# umodular_mega_shield_rev02.net
KiCad netlist of a schematic drawn in EAGLE
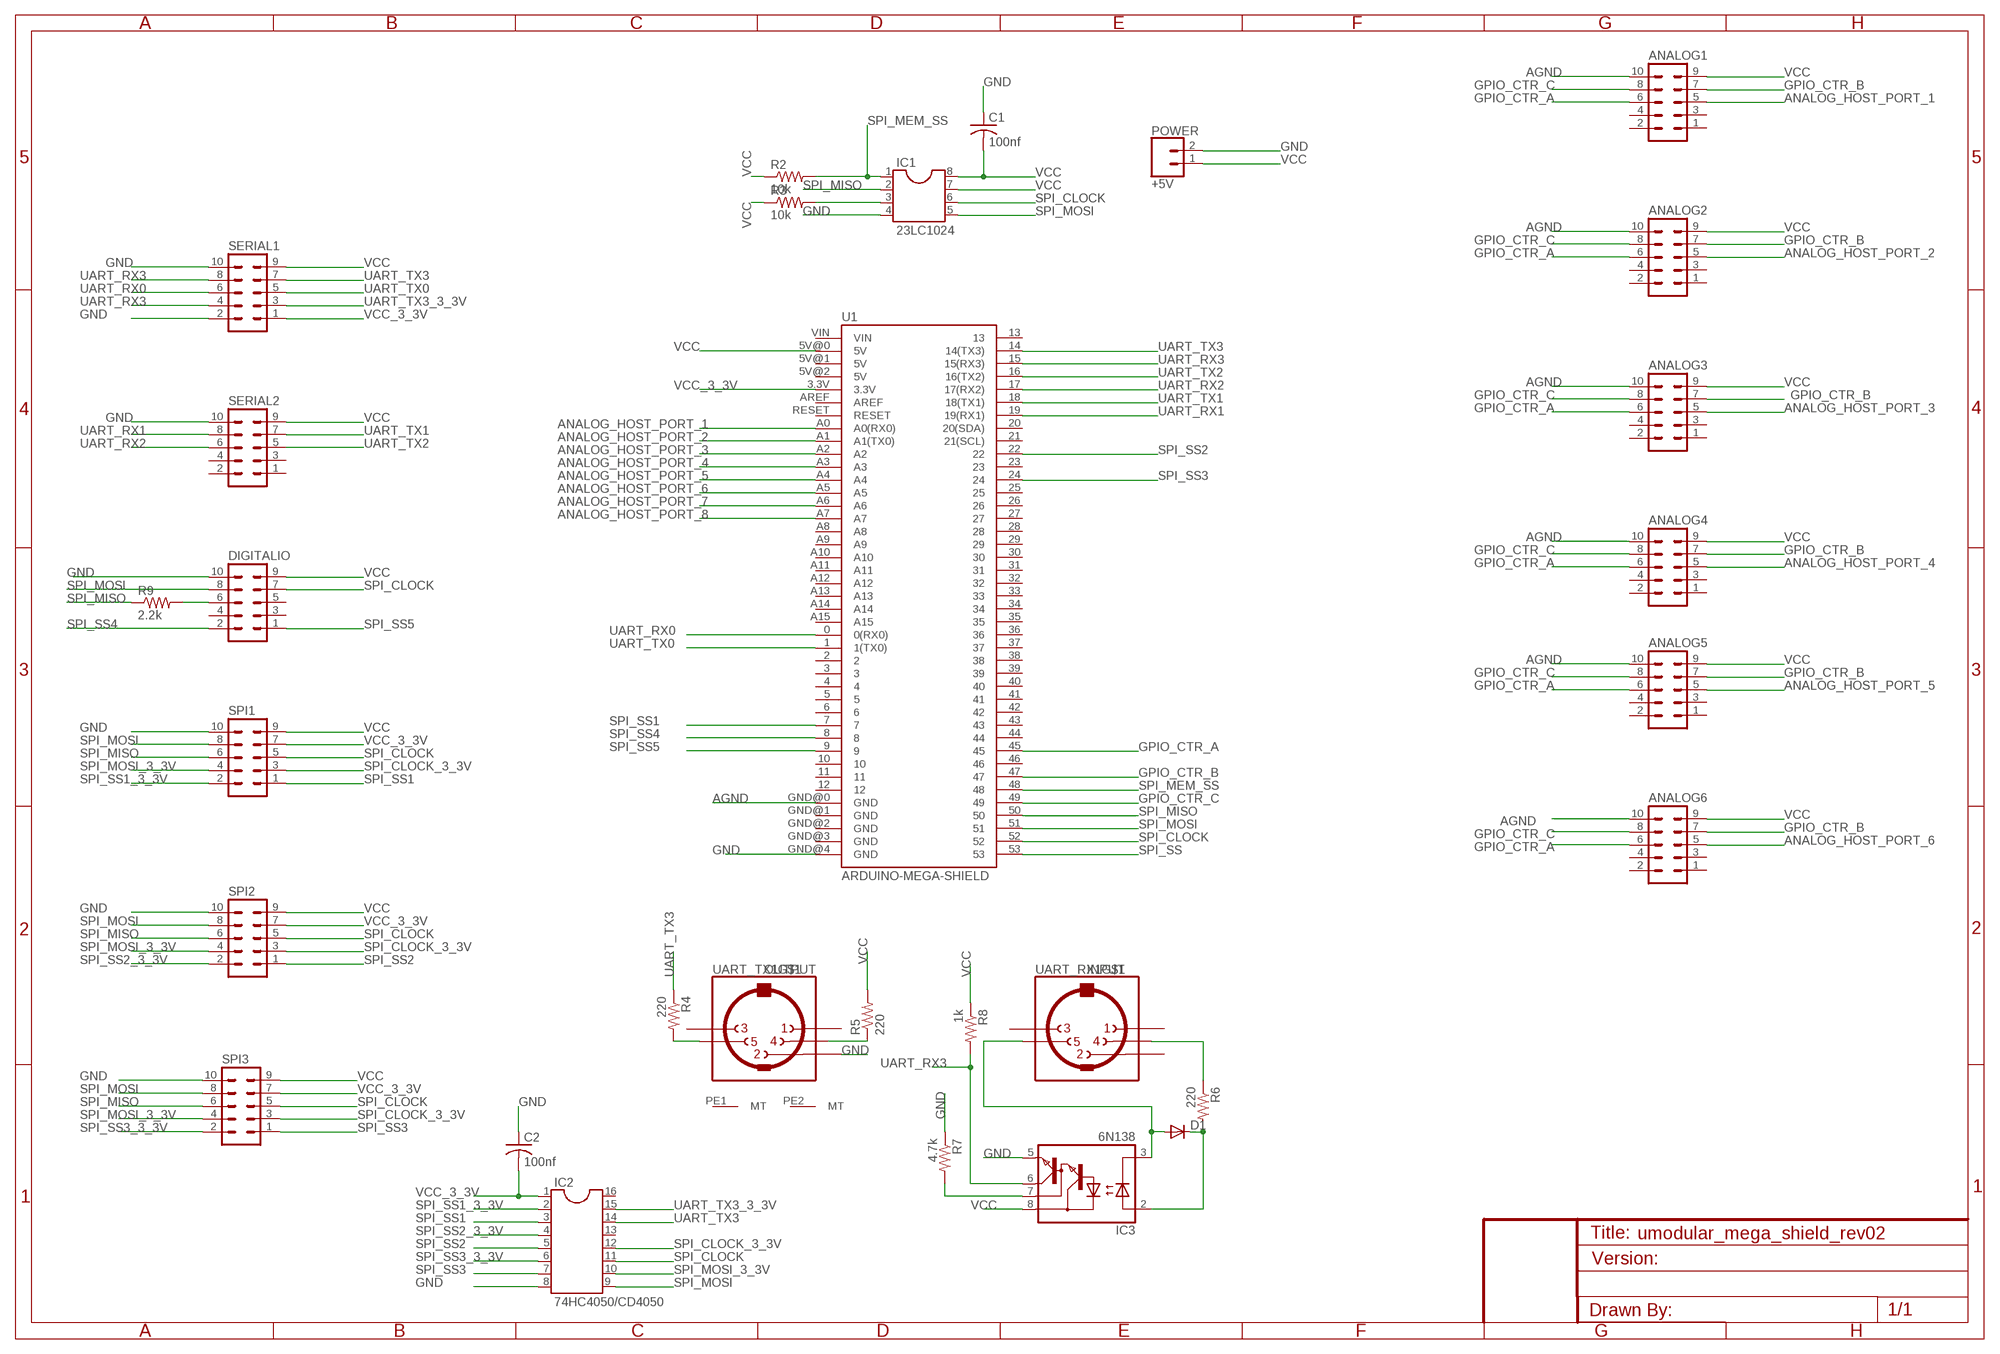
[diagram p0: schematic, sheet 1]

(export (version "E")
  (design (tool "Eeschema 10.0.6"))
  (components
    (comp (ref "ANALOG1")
      (value "MA05-2")
      (footprint "eagle-import:MA05-2")
      (libsource (lib "eagle-import") (part "MA05-2"))
    )
    (comp (ref "ANALOG2")
      (value "MA05-2")
      (footprint "eagle-import:MA05-2")
      (libsource (lib "eagle-import") (part "MA05-2"))
    )
    (comp (ref "ANALOG3")
      (value "MA05-2")
      (footprint "eagle-import:MA05-2")
      (libsource (lib "eagle-import") (part "MA05-2"))
    )
    (comp (ref "ANALOG4")
      (value "MA05-2")
      (footprint "eagle-import:MA05-2")
      (libsource (lib "eagle-import") (part "MA05-2"))
    )
    (comp (ref "ANALOG5")
      (value "MA05-2")
      (footprint "eagle-import:MA05-2")
      (libsource (lib "eagle-import") (part "MA05-2"))
    )
    (comp (ref "ANALOG6")
      (value "MA05-2")
      (footprint "eagle-import:MA05-2")
      (libsource (lib "eagle-import") (part "MA05-2"))
    )
    (comp (ref "C1")
      (value "100nf")
      (footprint "eagle-import:C050-024X044")
      (libsource (lib "eagle-import") (part "C-US050-024X044"))
    )
    (comp (ref "C2")
      (value "100nf")
      (footprint "eagle-import:C050-024X044")
      (libsource (lib "eagle-import") (part "C-US050-024X044"))
    )
    (comp (ref "D1")
      (value "1N4148DO35-7")
      (footprint "eagle-import:DO35-7")
      (libsource (lib "eagle-import") (part "1N4148DO35-7"))
    )
    (comp (ref "DIGITALIO")
      (value "MA05-2")
      (footprint "eagle-import:MA05-2")
      (libsource (lib "eagle-import") (part "MA05-2"))
    )
    (comp (ref "IC1")
      (value "23LC1024")
      (footprint "eagle-import:DIL08")
      (libsource (lib "eagle-import") (part "DIL8"))
    )
    (comp (ref "IC2")
      (value "74HC4050/CD4050")
      (footprint "eagle-import:DIL16")
      (libsource (lib "eagle-import") (part "DIL16"))
    )
    (comp (ref "IC3")
      (value "6N138")
      (footprint "eagle-import:DIL08")
      (fields (field (name "MF") "VISHAY/TELEFUNKEN"))
      (libsource (lib "eagle-import") (part "6N138"))
    )
    (comp (ref "POWER")
      (value "+5V")
      (footprint "eagle-import:1X02_LOCK_LONGPADS")
      (libsource (lib "eagle-import") (part "CONN_02LOCK_LONGPADS"))
    )
    (comp (ref "R2")
      (value "10k")
      (footprint "eagle-import:0204_7@1")
      (libsource (lib "eagle-import") (part "R-US_0204/7"))
    )
    (comp (ref "R3")
      (value "10k")
      (footprint "eagle-import:0204_7@1")
      (libsource (lib "eagle-import") (part "R-US_0204/7"))
    )
    (comp (ref "R4")
      (value "220")
      (footprint "eagle-import:0204_7@1")
      (libsource (lib "eagle-import") (part "R-US_0204/7"))
    )
    (comp (ref "R5")
      (value "220")
      (footprint "eagle-import:0204_7@1")
      (libsource (lib "eagle-import") (part "R-US_0204/7"))
    )
    (comp (ref "R6")
      (value "220")
      (footprint "eagle-import:0204_7@1")
      (libsource (lib "eagle-import") (part "R-US_0204/7"))
    )
    (comp (ref "R7")
      (value "4.7k")
      (footprint "eagle-import:0204_7@1")
      (libsource (lib "eagle-import") (part "R-US_0204/7"))
    )
    (comp (ref "R8")
      (value "1k")
      (footprint "eagle-import:0204_7@1")
      (libsource (lib "eagle-import") (part "R-US_0204/7"))
    )
    (comp (ref "R9")
      (value "2.2k")
      (footprint "eagle-import:0204_7@1")
      (libsource (lib "eagle-import") (part "R-US_0204/7"))
    )
    (comp (ref "SERIAL1")
      (value "MA05-2")
      (footprint "eagle-import:MA05-2")
      (libsource (lib "eagle-import") (part "MA05-2"))
    )
    (comp (ref "SERIAL2")
      (value "MA05-2")
      (footprint "eagle-import:MA05-2")
      (libsource (lib "eagle-import") (part "MA05-2"))
    )
    (comp (ref "SPI1")
      (value "MA05-2")
      (footprint "eagle-import:MA05-2")
      (libsource (lib "eagle-import") (part "MA05-2"))
    )
    (comp (ref "SPI2")
      (value "MA05-2")
      (footprint "eagle-import:MA05-2")
      (libsource (lib "eagle-import") (part "MA05-2"))
    )
    (comp (ref "SPI3")
      (value "MA05-2")
      (footprint "eagle-import:MA05-2")
      (libsource (lib "eagle-import") (part "MA05-2"))
    )
    (comp (ref "U1")
      (value "ARDUINO-MEGA-SHIELD")
      (footprint "eagle-import:ARDUINO_MEGA@1")
      (libsource (lib "eagle-import") (part "ARDUINO-MEGAFULL"))
    )
    (comp (ref "UART_RX1")
      (value "INPUT")
      (footprint "eagle-import:CP-2350")
      (libsource (lib "eagle-import") (part "MIDIJACK"))
    )
    (comp (ref "UART_TX1")
      (value "OUTPUT")
      (footprint "eagle-import:CP-2350")
      (libsource (lib "eagle-import") (part "MIDIJACK"))
    )
  )
  (nets
    (net (code "1") (name "/AGND") (class "Default")
      (node (ref "ANALOG1") (pin "10") (pinfunction "10_10") (pintype "passive"))
      (node (ref "ANALOG2") (pin "10") (pinfunction "10_10") (pintype "passive"))
      (node (ref "ANALOG3") (pin "10") (pinfunction "10_10") (pintype "passive"))
      (node (ref "ANALOG4") (pin "10") (pinfunction "10_10") (pintype "passive"))
      (node (ref "ANALOG5") (pin "10") (pinfunction "10_10") (pintype "passive"))
      (node (ref "ANALOG6") (pin "10") (pinfunction "10_10") (pintype "passive"))
      (node (ref "U1") (pin "GND@0") (pinfunction "GND_GND@0") (pintype "bidirectional"))
    )
    (net (code "2") (name "/ANALOG_HOST_PORT_1") (class "Default")
      (node (ref "ANALOG1") (pin "5") (pinfunction "5_5") (pintype "passive"))
      (node (ref "U1") (pin "A0") (pinfunction "A0(RX0)_A0") (pintype "bidirectional"))
    )
    (net (code "3") (name "/ANALOG_HOST_PORT_2") (class "Default")
      (node (ref "ANALOG2") (pin "5") (pinfunction "5_5") (pintype "passive"))
      (node (ref "U1") (pin "A1") (pinfunction "A1(TX0)_A1") (pintype "bidirectional"))
    )
    (net (code "4") (name "/ANALOG_HOST_PORT_3") (class "Default")
      (node (ref "ANALOG3") (pin "5") (pinfunction "5_5") (pintype "passive"))
      (node (ref "U1") (pin "A2") (pinfunction "A2_A2") (pintype "bidirectional"))
    )
    (net (code "5") (name "/ANALOG_HOST_PORT_4") (class "Default")
      (node (ref "ANALOG4") (pin "5") (pinfunction "5_5") (pintype "passive"))
      (node (ref "U1") (pin "A3") (pinfunction "A3_A3") (pintype "bidirectional"))
    )
    (net (code "6") (name "/ANALOG_HOST_PORT_5") (class "Default")
      (node (ref "ANALOG5") (pin "5") (pinfunction "5_5") (pintype "passive"))
      (node (ref "U1") (pin "A4") (pinfunction "A4_A4") (pintype "bidirectional"))
    )
    (net (code "7") (name "/ANALOG_HOST_PORT_6") (class "Default")
      (node (ref "ANALOG6") (pin "5") (pinfunction "5_5") (pintype "passive"))
      (node (ref "U1") (pin "A5") (pinfunction "A5_A5") (pintype "bidirectional"))
    )
    (net (code "8") (name "/ANALOG_HOST_PORT_7") (class "Default")
      (node (ref "U1") (pin "A6") (pinfunction "A6_A6") (pintype "bidirectional"))
    )
    (net (code "9") (name "/ANALOG_HOST_PORT_8") (class "Default")
      (node (ref "U1") (pin "A7") (pinfunction "A7_A7") (pintype "bidirectional"))
    )
    (net (code "10") (name "/GND") (class "Default")
      (node (ref "C1") (pin "1") (pinfunction "1_1") (pintype "passive"))
      (node (ref "C2") (pin "1") (pinfunction "1_1") (pintype "passive"))
      (node (ref "DIGITALIO") (pin "10") (pinfunction "10_10") (pintype "passive"))
      (node (ref "IC1") (pin "4") (pinfunction "4_4") (pintype "passive"))
      (node (ref "IC2") (pin "8") (pinfunction "8_8") (pintype "passive"))
      (node (ref "IC3") (pin "5") (pinfunction "GND_5") (pintype "passive"))
      (node (ref "POWER") (pin "2") (pinfunction "2_2") (pintype "passive"))
      (node (ref "R7") (pin "1") (pinfunction "1_1") (pintype "passive"))
      (node (ref "SERIAL1") (pin "10") (pinfunction "10_10") (pintype "passive"))
      (node (ref "SERIAL1") (pin "2") (pinfunction "2_2") (pintype "passive"))
      (node (ref "SERIAL2") (pin "10") (pinfunction "10_10") (pintype "passive"))
      (node (ref "SPI1") (pin "10") (pinfunction "10_10") (pintype "passive"))
      (node (ref "SPI2") (pin "10") (pinfunction "10_10") (pintype "passive"))
      (node (ref "SPI3") (pin "10") (pinfunction "10_10") (pintype "passive"))
      (node (ref "U1") (pin "GND@4") (pinfunction "GND_GND@4") (pintype "bidirectional"))
      (node (ref "UART_TX1") (pin "2") (pinfunction "2_2") (pintype "passive"))
    )
    (net (code "11") (name "/GPIO_CTR_A") (class "Default")
      (node (ref "ANALOG1") (pin "6") (pinfunction "6_6") (pintype "passive"))
      (node (ref "ANALOG2") (pin "6") (pinfunction "6_6") (pintype "passive"))
      (node (ref "ANALOG3") (pin "6") (pinfunction "6_6") (pintype "passive"))
      (node (ref "ANALOG4") (pin "6") (pinfunction "6_6") (pintype "passive"))
      (node (ref "ANALOG5") (pin "6") (pinfunction "6_6") (pintype "passive"))
      (node (ref "ANALOG6") (pin "6") (pinfunction "6_6") (pintype "passive"))
      (node (ref "U1") (pin "45") (pinfunction "45_45") (pintype "bidirectional"))
    )
    (net (code "12") (name "/GPIO_CTR_B") (class "Default")
      (node (ref "ANALOG1") (pin "7") (pinfunction "7_7") (pintype "passive"))
      (node (ref "ANALOG2") (pin "7") (pinfunction "7_7") (pintype "passive"))
      (node (ref "ANALOG3") (pin "7") (pinfunction "7_7") (pintype "passive"))
      (node (ref "ANALOG4") (pin "7") (pinfunction "7_7") (pintype "passive"))
      (node (ref "ANALOG5") (pin "7") (pinfunction "7_7") (pintype "passive"))
      (node (ref "ANALOG6") (pin "7") (pinfunction "7_7") (pintype "passive"))
      (node (ref "U1") (pin "47") (pinfunction "47_47") (pintype "bidirectional"))
    )
    (net (code "13") (name "/GPIO_CTR_C") (class "Default")
      (node (ref "ANALOG1") (pin "8") (pinfunction "8_8") (pintype "passive"))
      (node (ref "ANALOG2") (pin "8") (pinfunction "8_8") (pintype "passive"))
      (node (ref "ANALOG3") (pin "8") (pinfunction "8_8") (pintype "passive"))
      (node (ref "ANALOG4") (pin "8") (pinfunction "8_8") (pintype "passive"))
      (node (ref "ANALOG5") (pin "8") (pinfunction "8_8") (pintype "passive"))
      (node (ref "ANALOG6") (pin "8") (pinfunction "8_8") (pintype "passive"))
      (node (ref "U1") (pin "49") (pinfunction "49_49") (pintype "bidirectional"))
    )
    (net (code "14") (name "/SPI_CLOCK") (class "Default")
      (node (ref "DIGITALIO") (pin "7") (pinfunction "7_7") (pintype "passive"))
      (node (ref "IC1") (pin "6") (pinfunction "6_6") (pintype "passive"))
      (node (ref "IC2") (pin "11") (pinfunction "11_11") (pintype "passive"))
      (node (ref "SPI1") (pin "5") (pinfunction "5_5") (pintype "passive"))
      (node (ref "SPI2") (pin "5") (pinfunction "5_5") (pintype "passive"))
      (node (ref "SPI3") (pin "5") (pinfunction "5_5") (pintype "passive"))
      (node (ref "U1") (pin "52") (pinfunction "52_52") (pintype "bidirectional"))
    )
    (net (code "15") (name "/SPI_CLOCK_3_3V") (class "Default")
      (node (ref "IC2") (pin "12") (pinfunction "12_12") (pintype "passive"))
      (node (ref "SPI1") (pin "3") (pinfunction "3_3") (pintype "passive"))
      (node (ref "SPI2") (pin "3") (pinfunction "3_3") (pintype "passive"))
      (node (ref "SPI3") (pin "3") (pinfunction "3_3") (pintype "passive"))
    )
    (net (code "16") (name "/SPI_MEM_SS") (class "Default")
      (node (ref "IC1") (pin "1") (pinfunction "1_1") (pintype "passive"))
      (node (ref "R2") (pin "2") (pinfunction "2_2") (pintype "passive"))
      (node (ref "U1") (pin "48") (pinfunction "48_48") (pintype "bidirectional"))
    )
    (net (code "17") (name "/SPI_MISO") (class "Default")
      (node (ref "IC1") (pin "2") (pinfunction "2_2") (pintype "passive"))
      (node (ref "R9") (pin "1") (pinfunction "1_1") (pintype "passive"))
      (node (ref "SPI1") (pin "6") (pinfunction "6_6") (pintype "passive"))
      (node (ref "SPI2") (pin "6") (pinfunction "6_6") (pintype "passive"))
      (node (ref "SPI3") (pin "6") (pinfunction "6_6") (pintype "passive"))
      (node (ref "U1") (pin "50") (pinfunction "50_50") (pintype "bidirectional"))
    )
    (net (code "18") (name "/SPI_MOSI") (class "Default")
      (node (ref "DIGITALIO") (pin "8") (pinfunction "8_8") (pintype "passive"))
      (node (ref "IC1") (pin "5") (pinfunction "5_5") (pintype "passive"))
      (node (ref "IC2") (pin "9") (pinfunction "9_9") (pintype "passive"))
      (node (ref "SPI1") (pin "8") (pinfunction "8_8") (pintype "passive"))
      (node (ref "SPI2") (pin "8") (pinfunction "8_8") (pintype "passive"))
      (node (ref "SPI3") (pin "8") (pinfunction "8_8") (pintype "passive"))
      (node (ref "U1") (pin "51") (pinfunction "51_51") (pintype "bidirectional"))
    )
    (net (code "19") (name "/SPI_MOSI_3_3V") (class "Default")
      (node (ref "IC2") (pin "10") (pinfunction "10_10") (pintype "passive"))
      (node (ref "SPI1") (pin "4") (pinfunction "4_4") (pintype "passive"))
      (node (ref "SPI2") (pin "4") (pinfunction "4_4") (pintype "passive"))
      (node (ref "SPI3") (pin "4") (pinfunction "4_4") (pintype "passive"))
    )
    (net (code "20") (name "/SPI_SS") (class "Default")
      (node (ref "U1") (pin "53") (pinfunction "53_53") (pintype "bidirectional"))
    )
    (net (code "21") (name "/SPI_SS1") (class "Default")
      (node (ref "IC2") (pin "3") (pinfunction "3_3") (pintype "passive"))
      (node (ref "SPI1") (pin "1") (pinfunction "1_1") (pintype "passive"))
      (node (ref "U1") (pin "7") (pinfunction "7_7") (pintype "bidirectional"))
    )
    (net (code "22") (name "/SPI_SS1_3_3V") (class "Default")
      (node (ref "IC2") (pin "2") (pinfunction "2_2") (pintype "passive"))
      (node (ref "SPI1") (pin "2") (pinfunction "2_2") (pintype "passive"))
    )
    (net (code "23") (name "/SPI_SS2") (class "Default")
      (node (ref "IC2") (pin "5") (pinfunction "5_5") (pintype "passive"))
      (node (ref "SPI2") (pin "1") (pinfunction "1_1") (pintype "passive"))
      (node (ref "U1") (pin "22") (pinfunction "22_22") (pintype "bidirectional"))
    )
    (net (code "24") (name "/SPI_SS2_3_3V") (class "Default")
      (node (ref "IC2") (pin "4") (pinfunction "4_4") (pintype "passive"))
      (node (ref "SPI2") (pin "2") (pinfunction "2_2") (pintype "passive"))
    )
    (net (code "25") (name "/SPI_SS3") (class "Default")
      (node (ref "IC2") (pin "7") (pinfunction "7_7") (pintype "passive"))
      (node (ref "SPI3") (pin "1") (pinfunction "1_1") (pintype "passive"))
      (node (ref "U1") (pin "24") (pinfunction "24_24") (pintype "bidirectional"))
    )
    (net (code "26") (name "/SPI_SS3_3_3V") (class "Default")
      (node (ref "IC2") (pin "6") (pinfunction "6_6") (pintype "passive"))
      (node (ref "SPI3") (pin "2") (pinfunction "2_2") (pintype "passive"))
    )
    (net (code "27") (name "/SPI_SS4") (class "Default")
      (node (ref "DIGITALIO") (pin "2") (pinfunction "2_2") (pintype "passive"))
      (node (ref "U1") (pin "8") (pinfunction "8_8") (pintype "bidirectional"))
    )
    (net (code "28") (name "/SPI_SS5") (class "Default")
      (node (ref "DIGITALIO") (pin "1") (pinfunction "1_1") (pintype "passive"))
      (node (ref "U1") (pin "9") (pinfunction "9_9") (pintype "bidirectional"))
    )
    (net (code "29") (name "/UART_RX0") (class "Default")
      (node (ref "SERIAL1") (pin "6") (pinfunction "6_6") (pintype "passive"))
      (node (ref "U1") (pin "0") (pinfunction "0(RX0)_0") (pintype "bidirectional"))
    )
    (net (code "30") (name "/UART_RX1") (class "Default")
      (node (ref "SERIAL2") (pin "8") (pinfunction "8_8") (pintype "passive"))
      (node (ref "U1") (pin "19") (pinfunction "19(RX1)_19") (pintype "bidirectional"))
    )
    (net (code "31") (name "/UART_RX2") (class "Default")
      (node (ref "SERIAL2") (pin "6") (pinfunction "6_6") (pintype "passive"))
      (node (ref "U1") (pin "17") (pinfunction "17(RX2)_17") (pintype "bidirectional"))
    )
    (net (code "32") (name "/UART_RX3") (class "Default")
      (node (ref "IC3") (pin "6") (pinfunction "VO_6") (pintype "passive"))
      (node (ref "R8") (pin "2") (pinfunction "2_2") (pintype "passive"))
      (node (ref "SERIAL1") (pin "4") (pinfunction "4_4") (pintype "passive"))
      (node (ref "SERIAL1") (pin "8") (pinfunction "8_8") (pintype "passive"))
      (node (ref "U1") (pin "15") (pinfunction "15(RX3)_15") (pintype "bidirectional"))
    )
    (net (code "33") (name "/UART_TX0") (class "Default")
      (node (ref "SERIAL1") (pin "5") (pinfunction "5_5") (pintype "passive"))
      (node (ref "U1") (pin "1") (pinfunction "1(TX0)_1") (pintype "bidirectional"))
    )
    (net (code "34") (name "/UART_TX1") (class "Default")
      (node (ref "SERIAL2") (pin "7") (pinfunction "7_7") (pintype "passive"))
      (node (ref "U1") (pin "18") (pinfunction "18(TX1)_18") (pintype "bidirectional"))
    )
    (net (code "35") (name "/UART_TX2") (class "Default")
      (node (ref "SERIAL2") (pin "5") (pinfunction "5_5") (pintype "passive"))
      (node (ref "U1") (pin "16") (pinfunction "16(TX2)_16") (pintype "bidirectional"))
    )
    (net (code "36") (name "/UART_TX3") (class "Default")
      (node (ref "IC2") (pin "14") (pinfunction "14_14") (pintype "passive"))
      (node (ref "R4") (pin "1") (pinfunction "1_1") (pintype "passive"))
      (node (ref "SERIAL1") (pin "7") (pinfunction "7_7") (pintype "passive"))
      (node (ref "U1") (pin "14") (pinfunction "14(TX3)_14") (pintype "bidirectional"))
    )
    (net (code "37") (name "/UART_TX3_3_3V") (class "Default")
      (node (ref "IC2") (pin "15") (pinfunction "15_15") (pintype "passive"))
      (node (ref "SERIAL1") (pin "3") (pinfunction "3_3") (pintype "passive"))
    )
    (net (code "38") (name "/VCC") (class "Default")
      (node (ref "ANALOG1") (pin "9") (pinfunction "9_9") (pintype "passive"))
      (node (ref "ANALOG2") (pin "9") (pinfunction "9_9") (pintype "passive"))
      (node (ref "ANALOG3") (pin "9") (pinfunction "9_9") (pintype "passive"))
      (node (ref "ANALOG4") (pin "9") (pinfunction "9_9") (pintype "passive"))
      (node (ref "ANALOG5") (pin "9") (pinfunction "9_9") (pintype "passive"))
      (node (ref "ANALOG6") (pin "9") (pinfunction "9_9") (pintype "passive"))
      (node (ref "C1") (pin "2") (pinfunction "2_2") (pintype "passive"))
      (node (ref "DIGITALIO") (pin "9") (pinfunction "9_9") (pintype "passive"))
      (node (ref "IC1") (pin "7") (pinfunction "7_7") (pintype "passive"))
      (node (ref "IC1") (pin "8") (pinfunction "8_8") (pintype "passive"))
      (node (ref "IC3") (pin "8") (pinfunction "VCC_8") (pintype "passive"))
      (node (ref "POWER") (pin "1") (pinfunction "1_1") (pintype "passive"))
      (node (ref "R2") (pin "1") (pinfunction "1_1") (pintype "passive"))
      (node (ref "R3") (pin "1") (pinfunction "1_1") (pintype "passive"))
      (node (ref "R5") (pin "2") (pinfunction "2_2") (pintype "passive"))
      (node (ref "R8") (pin "1") (pinfunction "1_1") (pintype "passive"))
      (node (ref "SERIAL1") (pin "9") (pinfunction "9_9") (pintype "passive"))
      (node (ref "SERIAL2") (pin "9") (pinfunction "9_9") (pintype "passive"))
      (node (ref "SPI1") (pin "9") (pinfunction "9_9") (pintype "passive"))
      (node (ref "SPI2") (pin "9") (pinfunction "9_9") (pintype "passive"))
      (node (ref "SPI3") (pin "9") (pinfunction "9_9") (pintype "passive"))
      (node (ref "U1") (pin "5V@0") (pinfunction "5V_5V@0") (pintype "bidirectional"))
    )
    (net (code "39") (name "/VCC_3_3V") (class "Default")
      (node (ref "C2") (pin "2") (pinfunction "2_2") (pintype "passive"))
      (node (ref "IC2") (pin "1") (pinfunction "1_1") (pintype "passive"))
      (node (ref "SERIAL1") (pin "1") (pinfunction "1_1") (pintype "passive"))
      (node (ref "SPI1") (pin "7") (pinfunction "7_7") (pintype "passive"))
      (node (ref "SPI2") (pin "7") (pinfunction "7_7") (pintype "passive"))
      (node (ref "SPI3") (pin "7") (pinfunction "7_7") (pintype "passive"))
      (node (ref "U1") (pin "3.3V") (pinfunction "3.3V_3.3V") (pintype "bidirectional"))
    )
    (net (code "40") (name "Net-(DIGITALIO-Pad6)") (class "Default")
      (node (ref "DIGITALIO") (pin "6") (pinfunction "6_6") (pintype "passive"))
      (node (ref "R9") (pin "2") (pinfunction "2_2") (pintype "passive"))
    )
    (net (code "41") (name "Net-(IC1-Pad3)") (class "Default")
      (node (ref "IC1") (pin "3") (pinfunction "3_3") (pintype "passive"))
      (node (ref "R3") (pin "2") (pinfunction "2_2") (pintype "passive"))
    )
    (net (code "42") (name "Net-(IC3-A)") (class "Default")
      (node (ref "D1") (pin "C") (pinfunction "C_C") (pintype "passive"))
      (node (ref "IC3") (pin "2") (pinfunction "A_2") (pintype "passive"))
      (node (ref "R6") (pin "2") (pinfunction "2_2") (pintype "passive"))
    )
    (net (code "43") (name "Net-(IC3-C)") (class "Default")
      (node (ref "D1") (pin "A") (pinfunction "A_A") (pintype "passive"))
      (node (ref "IC3") (pin "3") (pinfunction "C_3") (pintype "passive"))
      (node (ref "UART_RX1") (pin "5") (pinfunction "5_5") (pintype "passive"))
    )
    (net (code "44") (name "Net-(IC3-VB)") (class "Default")
      (node (ref "IC3") (pin "7") (pinfunction "VB_7") (pintype "passive"))
      (node (ref "R7") (pin "2") (pinfunction "2_2") (pintype "passive"))
    )
    (net (code "45") (name "Net-(R4-Pad2)") (class "Default")
      (node (ref "R4") (pin "2") (pinfunction "2_2") (pintype "passive"))
      (node (ref "UART_TX1") (pin "5") (pinfunction "5_5") (pintype "passive"))
    )
    (net (code "46") (name "Net-(R5-Pad1)") (class "Default")
      (node (ref "R5") (pin "1") (pinfunction "1_1") (pintype "passive"))
      (node (ref "UART_TX1") (pin "4") (pinfunction "4_4") (pintype "passive"))
    )
    (net (code "47") (name "Net-(R6-Pad1)") (class "Default")
      (node (ref "R6") (pin "1") (pinfunction "1_1") (pintype "passive"))
      (node (ref "UART_RX1") (pin "4") (pinfunction "4_4") (pintype "passive"))
    )
    (net (code "48") (name "unconnected-(ANALOG1-Pad1)") (class "Default")
      (node (ref "ANALOG1") (pin "1") (pinfunction "1_1") (pintype "passive"))
    )
    (net (code "49") (name "unconnected-(ANALOG1-Pad2)") (class "Default")
      (node (ref "ANALOG1") (pin "2") (pinfunction "2_2") (pintype "passive"))
    )
    (net (code "50") (name "unconnected-(ANALOG1-Pad3)") (class "Default")
      (node (ref "ANALOG1") (pin "3") (pinfunction "3_3") (pintype "passive"))
    )
    (net (code "51") (name "unconnected-(ANALOG1-Pad4)") (class "Default")
      (node (ref "ANALOG1") (pin "4") (pinfunction "4_4") (pintype "passive"))
    )
    (net (code "52") (name "unconnected-(ANALOG2-Pad1)") (class "Default")
      (node (ref "ANALOG2") (pin "1") (pinfunction "1_1") (pintype "passive"))
    )
    (net (code "53") (name "unconnected-(ANALOG2-Pad2)") (class "Default")
      (node (ref "ANALOG2") (pin "2") (pinfunction "2_2") (pintype "passive"))
    )
    (net (code "54") (name "unconnected-(ANALOG2-Pad3)") (class "Default")
      (node (ref "ANALOG2") (pin "3") (pinfunction "3_3") (pintype "passive"))
    )
    (net (code "55") (name "unconnected-(ANALOG2-Pad4)") (class "Default")
      (node (ref "ANALOG2") (pin "4") (pinfunction "4_4") (pintype "passive"))
    )
    (net (code "56") (name "unconnected-(ANALOG3-Pad1)") (class "Default")
      (node (ref "ANALOG3") (pin "1") (pinfunction "1_1") (pintype "passive"))
    )
    (net (code "57") (name "unconnected-(ANALOG3-Pad2)") (class "Default")
      (node (ref "ANALOG3") (pin "2") (pinfunction "2_2") (pintype "passive"))
    )
    (net (code "58") (name "unconnected-(ANALOG3-Pad3)") (class "Default")
      (node (ref "ANALOG3") (pin "3") (pinfunction "3_3") (pintype "passive"))
    )
    (net (code "59") (name "unconnected-(ANALOG3-Pad4)") (class "Default")
      (node (ref "ANALOG3") (pin "4") (pinfunction "4_4") (pintype "passive"))
    )
    (net (code "60") (name "unconnected-(ANALOG4-Pad1)") (class "Default")
      (node (ref "ANALOG4") (pin "1") (pinfunction "1_1") (pintype "passive"))
    )
    (net (code "61") (name "unconnected-(ANALOG4-Pad2)") (class "Default")
      (node (ref "ANALOG4") (pin "2") (pinfunction "2_2") (pintype "passive"))
    )
    (net (code "62") (name "unconnected-(ANALOG4-Pad3)") (class "Default")
      (node (ref "ANALOG4") (pin "3") (pinfunction "3_3") (pintype "passive"))
    )
    (net (code "63") (name "unconnected-(ANALOG4-Pad4)") (class "Default")
      (node (ref "ANALOG4") (pin "4") (pinfunction "4_4") (pintype "passive"))
    )
    (net (code "64") (name "unconnected-(ANALOG5-Pad1)") (class "Default")
      (node (ref "ANALOG5") (pin "1") (pinfunction "1_1") (pintype "passive"))
    )
    (net (code "65") (name "unconnected-(ANALOG5-Pad2)") (class "Default")
      (node (ref "ANALOG5") (pin "2") (pinfunction "2_2") (pintype "passive"))
    )
    (net (code "66") (name "unconnected-(ANALOG5-Pad3)") (class "Default")
      (node (ref "ANALOG5") (pin "3") (pinfunction "3_3") (pintype "passive"))
    )
    (net (code "67") (name "unconnected-(ANALOG5-Pad4)") (class "Default")
      (node (ref "ANALOG5") (pin "4") (pinfunction "4_4") (pintype "passive"))
    )
    (net (code "68") (name "unconnected-(ANALOG6-Pad1)") (class "Default")
      (node (ref "ANALOG6") (pin "1") (pinfunction "1_1") (pintype "passive"))
    )
    (net (code "69") (name "unconnected-(ANALOG6-Pad2)") (class "Default")
      (node (ref "ANALOG6") (pin "2") (pinfunction "2_2") (pintype "passive"))
    )
    (net (code "70") (name "unconnected-(ANALOG6-Pad3)") (class "Default")
      (node (ref "ANALOG6") (pin "3") (pinfunction "3_3") (pintype "passive"))
    )
    (net (code "71") (name "unconnected-(ANALOG6-Pad4)") (class "Default")
      (node (ref "ANALOG6") (pin "4") (pinfunction "4_4") (pintype "passive"))
    )
    (net (code "72") (name "unconnected-(DIGITALIO-Pad3)") (class "Default")
      (node (ref "DIGITALIO") (pin "3") (pinfunction "3_3") (pintype "passive"))
    )
    (net (code "73") (name "unconnected-(DIGITALIO-Pad4)") (class "Default")
      (node (ref "DIGITALIO") (pin "4") (pinfunction "4_4") (pintype "passive"))
    )
    (net (code "74") (name "unconnected-(DIGITALIO-Pad5)") (class "Default")
      (node (ref "DIGITALIO") (pin "5") (pinfunction "5_5") (pintype "passive"))
    )
    (net (code "75") (name "unconnected-(IC2-Pad13)") (class "Default")
      (node (ref "IC2") (pin "13") (pinfunction "13_13") (pintype "passive"))
    )
    (net (code "76") (name "unconnected-(IC2-Pad16)") (class "Default")
      (node (ref "IC2") (pin "16") (pinfunction "16_16") (pintype "passive"))
    )
    (net (code "77") (name "unconnected-(SERIAL2-Pad1)") (class "Default")
      (node (ref "SERIAL2") (pin "1") (pinfunction "1_1") (pintype "passive"))
    )
    (net (code "78") (name "unconnected-(SERIAL2-Pad2)") (class "Default")
      (node (ref "SERIAL2") (pin "2") (pinfunction "2_2") (pintype "passive"))
    )
    (net (code "79") (name "unconnected-(SERIAL2-Pad3)") (class "Default")
      (node (ref "SERIAL2") (pin "3") (pinfunction "3_3") (pintype "passive"))
    )
    (net (code "80") (name "unconnected-(SERIAL2-Pad4)") (class "Default")
      (node (ref "SERIAL2") (pin "4") (pinfunction "4_4") (pintype "passive"))
    )
    (net (code "81") (name "unconnected-(U1-5V-Pad5V@1)") (class "Default")
      (node (ref "U1") (pin "5V@1") (pinfunction "5V_5V@1") (pintype "bidirectional"))
    )
    (net (code "82") (name "unconnected-(U1-5V-Pad5V@2)") (class "Default")
      (node (ref "U1") (pin "5V@2") (pinfunction "5V_5V@2") (pintype "bidirectional"))
    )
    (net (code "83") (name "unconnected-(U1-20(SDA)-Pad20)") (class "Default")
      (node (ref "U1") (pin "20") (pinfunction "20(SDA)_20") (pintype "bidirectional"))
    )
    (net (code "84") (name "unconnected-(U1-21(SCL)-Pad21)") (class "Default")
      (node (ref "U1") (pin "21") (pinfunction "21(SCL)_21") (pintype "bidirectional"))
    )
    (net (code "85") (name "unconnected-(U1-GND-PadGND@1)") (class "Default")
      (node (ref "U1") (pin "GND@1") (pinfunction "GND_GND@1") (pintype "bidirectional"))
    )
    (net (code "86") (name "unconnected-(U1-GND-PadGND@2)") (class "Default")
      (node (ref "U1") (pin "GND@2") (pinfunction "GND_GND@2") (pintype "bidirectional"))
    )
    (net (code "87") (name "unconnected-(U1-GND-PadGND@3)") (class "Default")
      (node (ref "U1") (pin "GND@3") (pinfunction "GND_GND@3") (pintype "bidirectional"))
    )
    (net (code "88") (name "unconnected-(U1-Pad2)") (class "Default")
      (node (ref "U1") (pin "2") (pinfunction "2_2") (pintype "bidirectional"))
    )
    (net (code "89") (name "unconnected-(U1-Pad3)") (class "Default")
      (node (ref "U1") (pin "3") (pinfunction "3_3") (pintype "bidirectional"))
    )
    (net (code "90") (name "unconnected-(U1-Pad4)") (class "Default")
      (node (ref "U1") (pin "4") (pinfunction "4_4") (pintype "bidirectional"))
    )
    (net (code "91") (name "unconnected-(U1-Pad5)") (class "Default")
      (node (ref "U1") (pin "5") (pinfunction "5_5") (pintype "bidirectional"))
    )
    (net (code "92") (name "unconnected-(U1-Pad6)") (class "Default")
      (node (ref "U1") (pin "6") (pinfunction "6_6") (pintype "bidirectional"))
    )
    (net (code "93") (name "unconnected-(U1-Pad10)") (class "Default")
      (node (ref "U1") (pin "10") (pinfunction "10_10") (pintype "bidirectional"))
    )
    (net (code "94") (name "unconnected-(U1-Pad11)") (class "Default")
      (node (ref "U1") (pin "11") (pinfunction "11_11") (pintype "bidirectional"))
    )
    (net (code "95") (name "unconnected-(U1-Pad12)") (class "Default")
      (node (ref "U1") (pin "12") (pinfunction "12_12") (pintype "bidirectional"))
    )
    (net (code "96") (name "unconnected-(U1-Pad13)") (class "Default")
      (node (ref "U1") (pin "13") (pinfunction "13_13") (pintype "bidirectional"))
    )
    (net (code "97") (name "unconnected-(U1-Pad23)") (class "Default")
      (node (ref "U1") (pin "23") (pinfunction "23_23") (pintype "bidirectional"))
    )
    (net (code "98") (name "unconnected-(U1-Pad25)") (class "Default")
      (node (ref "U1") (pin "25") (pinfunction "25_25") (pintype "bidirectional"))
    )
    (net (code "99") (name "unconnected-(U1-Pad26)") (class "Default")
      (node (ref "U1") (pin "26") (pinfunction "26_26") (pintype "bidirectional"))
    )
    (net (code "100") (name "unconnected-(U1-Pad27)") (class "Default")
      (node (ref "U1") (pin "27") (pinfunction "27_27") (pintype "bidirectional"))
    )
    (net (code "101") (name "unconnected-(U1-Pad28)") (class "Default")
      (node (ref "U1") (pin "28") (pinfunction "28_28") (pintype "bidirectional"))
    )
    (net (code "102") (name "unconnected-(U1-Pad29)") (class "Default")
      (node (ref "U1") (pin "29") (pinfunction "29_29") (pintype "bidirectional"))
    )
    (net (code "103") (name "unconnected-(U1-Pad30)") (class "Default")
      (node (ref "U1") (pin "30") (pinfunction "30_30") (pintype "bidirectional"))
    )
    (net (code "104") (name "unconnected-(U1-Pad31)") (class "Default")
      (node (ref "U1") (pin "31") (pinfunction "31_31") (pintype "bidirectional"))
    )
    (net (code "105") (name "unconnected-(U1-Pad32)") (class "Default")
      (node (ref "U1") (pin "32") (pinfunction "32_32") (pintype "bidirectional"))
    )
    (net (code "106") (name "unconnected-(U1-Pad33)") (class "Default")
      (node (ref "U1") (pin "33") (pinfunction "33_33") (pintype "bidirectional"))
    )
    (net (code "107") (name "unconnected-(U1-Pad34)") (class "Default")
      (node (ref "U1") (pin "34") (pinfunction "34_34") (pintype "bidirectional"))
    )
    (net (code "108") (name "unconnected-(U1-Pad35)") (class "Default")
      (node (ref "U1") (pin "35") (pinfunction "35_35") (pintype "bidirectional"))
    )
    (net (code "109") (name "unconnected-(U1-Pad36)") (class "Default")
      (node (ref "U1") (pin "36") (pinfunction "36_36") (pintype "bidirectional"))
    )
    (net (code "110") (name "unconnected-(U1-Pad37)") (class "Default")
      (node (ref "U1") (pin "37") (pinfunction "37_37") (pintype "bidirectional"))
    )
    (net (code "111") (name "unconnected-(U1-Pad38)") (class "Default")
      (node (ref "U1") (pin "38") (pinfunction "38_38") (pintype "bidirectional"))
    )
    (net (code "112") (name "unconnected-(U1-Pad39)") (class "Default")
      (node (ref "U1") (pin "39") (pinfunction "39_39") (pintype "bidirectional"))
    )
    (net (code "113") (name "unconnected-(U1-Pad40)") (class "Default")
      (node (ref "U1") (pin "40") (pinfunction "40_40") (pintype "bidirectional"))
    )
    (net (code "114") (name "unconnected-(U1-Pad41)") (class "Default")
      (node (ref "U1") (pin "41") (pinfunction "41_41") (pintype "bidirectional"))
    )
    (net (code "115") (name "unconnected-(U1-Pad42)") (class "Default")
      (node (ref "U1") (pin "42") (pinfunction "42_42") (pintype "bidirectional"))
    )
    (net (code "116") (name "unconnected-(U1-Pad43)") (class "Default")
      (node (ref "U1") (pin "43") (pinfunction "43_43") (pintype "bidirectional"))
    )
    (net (code "117") (name "unconnected-(U1-Pad44)") (class "Default")
      (node (ref "U1") (pin "44") (pinfunction "44_44") (pintype "bidirectional"))
    )
    (net (code "118") (name "unconnected-(U1-Pad46)") (class "Default")
      (node (ref "U1") (pin "46") (pinfunction "46_46") (pintype "bidirectional"))
    )
    (net (code "119") (name "unconnected-(U1-PadA8)") (class "Default")
      (node (ref "U1") (pin "A8") (pinfunction "A8_A8") (pintype "bidirectional"))
    )
    (net (code "120") (name "unconnected-(U1-PadA9)") (class "Default")
      (node (ref "U1") (pin "A9") (pinfunction "A9_A9") (pintype "bidirectional"))
    )
    (net (code "121") (name "unconnected-(U1-PadA10)") (class "Default")
      (node (ref "U1") (pin "A10") (pinfunction "A10_A10") (pintype "bidirectional"))
    )
    (net (code "122") (name "unconnected-(U1-PadA11)") (class "Default")
      (node (ref "U1") (pin "A11") (pinfunction "A11_A11") (pintype "bidirectional"))
    )
    (net (code "123") (name "unconnected-(U1-PadA12)") (class "Default")
      (node (ref "U1") (pin "A12") (pinfunction "A12_A12") (pintype "bidirectional"))
    )
    (net (code "124") (name "unconnected-(U1-PadA13)") (class "Default")
      (node (ref "U1") (pin "A13") (pinfunction "A13_A13") (pintype "bidirectional"))
    )
    (net (code "125") (name "unconnected-(U1-PadA14)") (class "Default")
      (node (ref "U1") (pin "A14") (pinfunction "A14_A14") (pintype "bidirectional"))
    )
    (net (code "126") (name "unconnected-(U1-PadA15)") (class "Default")
      (node (ref "U1") (pin "A15") (pinfunction "A15_A15") (pintype "bidirectional"))
    )
    (net (code "127") (name "unconnected-(U1-PadAREF)") (class "Default")
      (node (ref "U1") (pin "AREF") (pinfunction "AREF_AREF") (pintype "bidirectional"))
    )
    (net (code "128") (name "unconnected-(U1-PadRESET)") (class "Default")
      (node (ref "U1") (pin "RESET") (pinfunction "RESET_RESET") (pintype "bidirectional"))
    )
    (net (code "129") (name "unconnected-(U1-PadVIN)") (class "Default")
      (node (ref "U1") (pin "VIN") (pinfunction "VIN_VIN") (pintype "bidirectional"))
    )
    (net (code "130") (name "unconnected-(UART_RX1-Pad1)") (class "Default")
      (node (ref "UART_RX1") (pin "1") (pinfunction "1_1") (pintype "passive"))
    )
    (net (code "131") (name "unconnected-(UART_RX1-Pad2)") (class "Default")
      (node (ref "UART_RX1") (pin "2") (pinfunction "2_2") (pintype "passive"))
    )
    (net (code "132") (name "unconnected-(UART_RX1-Pad3)") (class "Default")
      (node (ref "UART_RX1") (pin "3") (pinfunction "3_3") (pintype "passive"))
    )
    (net (code "133") (name "unconnected-(UART_TX1-Pad1)") (class "Default")
      (node (ref "UART_TX1") (pin "1") (pinfunction "1_1") (pintype "passive"))
    )
    (net (code "134") (name "unconnected-(UART_TX1-Pad3)") (class "Default")
      (node (ref "UART_TX1") (pin "3") (pinfunction "3_3") (pintype "passive"))
    )
    (net (code "135") (name "unconnected-(UART_TX1D-MT-PadPE1)") (class "Default")
      (node (ref "UART_TX1") (pin "PE1") (pinfunction "MT_PE1") (pintype "passive"))
    )
    (net (code "136") (name "unconnected-(UART_TX1E-MT-PadPE2)") (class "Default")
      (node (ref "UART_TX1") (pin "PE2") (pinfunction "MT_PE2") (pintype "passive"))
    )
  )
)
